# ADIS16209_Practice_Board.net
KiCad netlist of a schematic drawn in EAGLE
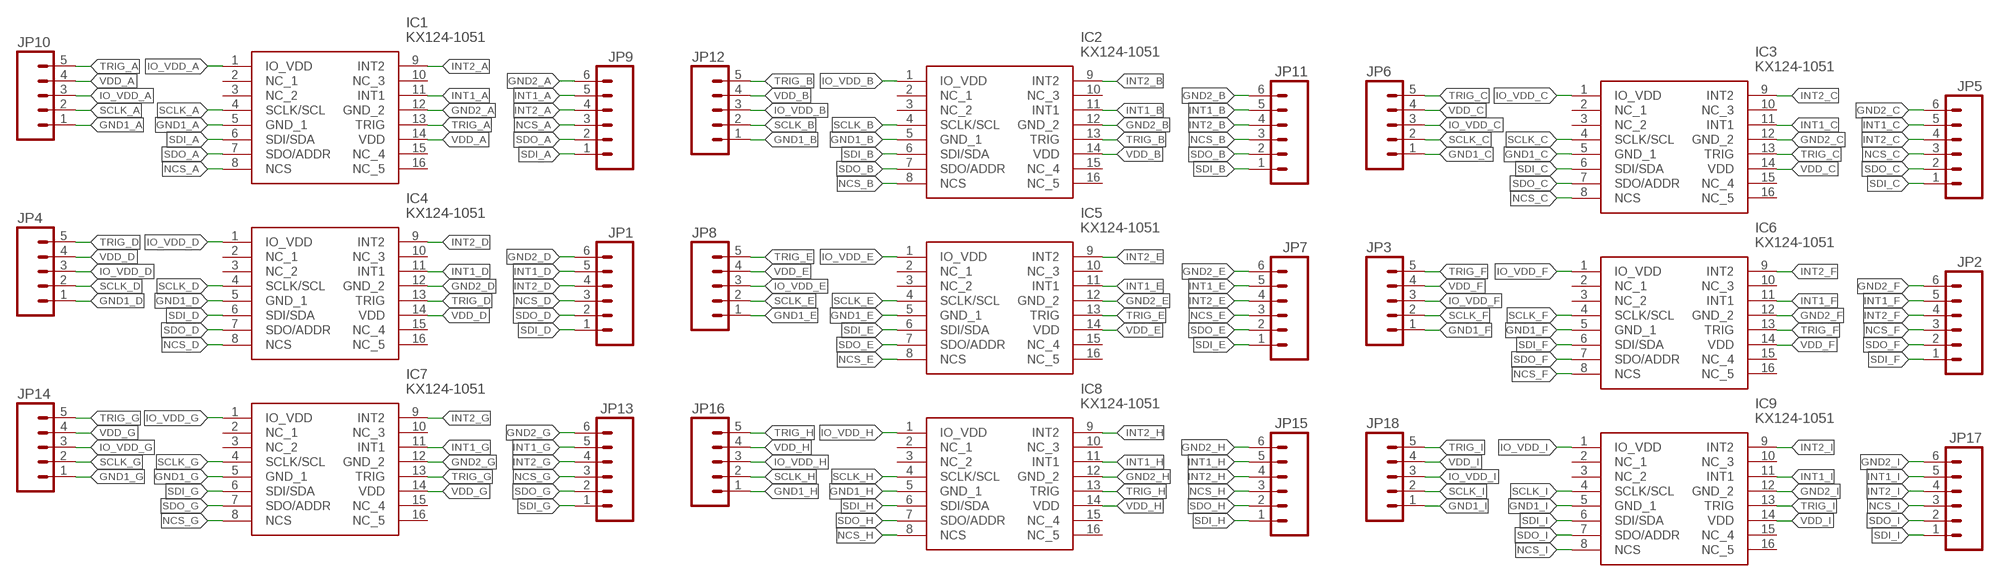
[diagram p0: schematic, sheet 1]

(export (version "E")
  (design (tool "Eeschema 10.0.6"))
  (components
    (comp (ref "IC1")
      (value "KX124-1051")
      (footprint "eagle-import:3X3LGA")
      (fields (field (name "MOUSER_PART_NUMBER") "912-KX124-1051-FR"))
      (libsource (lib "eagle-import") (part "KX124-1051"))
    )
    (comp (ref "IC2")
      (value "KX124-1051")
      (footprint "eagle-import:3X3LGA")
      (fields (field (name "MOUSER_PART_NUMBER") "912-KX124-1051-FR"))
      (libsource (lib "eagle-import") (part "KX124-1051"))
    )
    (comp (ref "IC3")
      (value "KX124-1051")
      (footprint "eagle-import:3X3LGA")
      (fields (field (name "MOUSER_PART_NUMBER") "912-KX124-1051-FR"))
      (libsource (lib "eagle-import") (part "KX124-1051"))
    )
    (comp (ref "IC4")
      (value "KX124-1051")
      (footprint "eagle-import:3X3LGA")
      (fields (field (name "MOUSER_PART_NUMBER") "912-KX124-1051-FR"))
      (libsource (lib "eagle-import") (part "KX124-1051"))
    )
    (comp (ref "IC5")
      (value "KX124-1051")
      (footprint "eagle-import:3X3LGA")
      (fields (field (name "MOUSER_PART_NUMBER") "912-KX124-1051-FR"))
      (libsource (lib "eagle-import") (part "KX124-1051"))
    )
    (comp (ref "IC6")
      (value "KX124-1051")
      (footprint "eagle-import:3X3LGA")
      (fields (field (name "MOUSER_PART_NUMBER") "912-KX124-1051-FR"))
      (libsource (lib "eagle-import") (part "KX124-1051"))
    )
    (comp (ref "IC7")
      (value "KX124-1051")
      (footprint "eagle-import:3X3LGA")
      (fields (field (name "MOUSER_PART_NUMBER") "912-KX124-1051-FR"))
      (libsource (lib "eagle-import") (part "KX124-1051"))
    )
    (comp (ref "IC8")
      (value "KX124-1051")
      (footprint "eagle-import:3X3LGA")
      (fields (field (name "MOUSER_PART_NUMBER") "912-KX124-1051-FR"))
      (libsource (lib "eagle-import") (part "KX124-1051"))
    )
    (comp (ref "IC9")
      (value "KX124-1051")
      (footprint "eagle-import:3X3LGA")
      (fields (field (name "MOUSER_PART_NUMBER") "912-KX124-1051-FR"))
      (libsource (lib "eagle-import") (part "KX124-1051"))
    )
    (comp (ref "JP1")
      (value "M06")
      (footprint "eagle-import:1X06")
      (libsource (lib "eagle-import") (part "M06"))
    )
    (comp (ref "JP2")
      (value "M06")
      (footprint "eagle-import:1X06")
      (libsource (lib "eagle-import") (part "M06"))
    )
    (comp (ref "JP3")
      (value "M05")
      (footprint "eagle-import:1X05")
      (libsource (lib "eagle-import") (part "M05"))
    )
    (comp (ref "JP4")
      (value "M05")
      (footprint "eagle-import:1X05")
      (libsource (lib "eagle-import") (part "M05"))
    )
    (comp (ref "JP5")
      (value "M06")
      (footprint "eagle-import:1X06")
      (libsource (lib "eagle-import") (part "M06"))
    )
    (comp (ref "JP6")
      (value "M05")
      (footprint "eagle-import:1X05")
      (libsource (lib "eagle-import") (part "M05"))
    )
    (comp (ref "JP7")
      (value "M06")
      (footprint "eagle-import:1X06")
      (libsource (lib "eagle-import") (part "M06"))
    )
    (comp (ref "JP8")
      (value "M05")
      (footprint "eagle-import:1X05")
      (libsource (lib "eagle-import") (part "M05"))
    )
    (comp (ref "JP9")
      (value "M06")
      (footprint "eagle-import:1X06")
      (libsource (lib "eagle-import") (part "M06"))
    )
    (comp (ref "JP10")
      (value "M05")
      (footprint "eagle-import:1X05")
      (libsource (lib "eagle-import") (part "M05"))
    )
    (comp (ref "JP11")
      (value "M06")
      (footprint "eagle-import:1X06")
      (libsource (lib "eagle-import") (part "M06"))
    )
    (comp (ref "JP12")
      (value "M05")
      (footprint "eagle-import:1X05")
      (libsource (lib "eagle-import") (part "M05"))
    )
    (comp (ref "JP13")
      (value "M06")
      (footprint "eagle-import:1X06")
      (libsource (lib "eagle-import") (part "M06"))
    )
    (comp (ref "JP14")
      (value "M05")
      (footprint "eagle-import:1X05")
      (libsource (lib "eagle-import") (part "M05"))
    )
    (comp (ref "JP15")
      (value "M06")
      (footprint "eagle-import:1X06")
      (libsource (lib "eagle-import") (part "M06"))
    )
    (comp (ref "JP16")
      (value "M05")
      (footprint "eagle-import:1X05")
      (libsource (lib "eagle-import") (part "M05"))
    )
    (comp (ref "JP17")
      (value "M06")
      (footprint "eagle-import:1X06")
      (libsource (lib "eagle-import") (part "M06"))
    )
    (comp (ref "JP18")
      (value "M05")
      (footprint "eagle-import:1X05")
      (libsource (lib "eagle-import") (part "M05"))
    )
  )
  (nets
    (net (code "1") (name "GND1_A") (class "Default")
      (node (ref "IC1") (pin "5") (pinfunction "GND_1_5") (pintype "bidirectional"))
      (node (ref "JP10") (pin "1") (pinfunction "1_1") (pintype "passive"))
    )
    (net (code "2") (name "GND1_B") (class "Default")
      (node (ref "IC2") (pin "5") (pinfunction "GND_1_5") (pintype "bidirectional"))
      (node (ref "JP12") (pin "1") (pinfunction "1_1") (pintype "passive"))
    )
    (net (code "3") (name "GND1_C") (class "Default")
      (node (ref "IC3") (pin "5") (pinfunction "GND_1_5") (pintype "bidirectional"))
      (node (ref "JP6") (pin "1") (pinfunction "1_1") (pintype "passive"))
    )
    (net (code "4") (name "GND1_D") (class "Default")
      (node (ref "IC4") (pin "5") (pinfunction "GND_1_5") (pintype "bidirectional"))
      (node (ref "JP4") (pin "1") (pinfunction "1_1") (pintype "passive"))
    )
    (net (code "5") (name "GND1_E") (class "Default")
      (node (ref "IC5") (pin "5") (pinfunction "GND_1_5") (pintype "bidirectional"))
      (node (ref "JP8") (pin "1") (pinfunction "1_1") (pintype "passive"))
    )
    (net (code "6") (name "GND1_F") (class "Default")
      (node (ref "IC6") (pin "5") (pinfunction "GND_1_5") (pintype "bidirectional"))
      (node (ref "JP3") (pin "1") (pinfunction "1_1") (pintype "passive"))
    )
    (net (code "7") (name "GND1_G") (class "Default")
      (node (ref "IC7") (pin "5") (pinfunction "GND_1_5") (pintype "bidirectional"))
      (node (ref "JP14") (pin "1") (pinfunction "1_1") (pintype "passive"))
    )
    (net (code "8") (name "GND1_H") (class "Default")
      (node (ref "IC8") (pin "5") (pinfunction "GND_1_5") (pintype "bidirectional"))
      (node (ref "JP16") (pin "1") (pinfunction "1_1") (pintype "passive"))
    )
    (net (code "9") (name "GND1_I") (class "Default")
      (node (ref "IC9") (pin "5") (pinfunction "GND_1_5") (pintype "bidirectional"))
      (node (ref "JP18") (pin "1") (pinfunction "1_1") (pintype "passive"))
    )
    (net (code "10") (name "GND2_A") (class "Default")
      (node (ref "IC1") (pin "12") (pinfunction "GND_2_12") (pintype "bidirectional"))
      (node (ref "JP9") (pin "6") (pinfunction "6_6") (pintype "passive"))
    )
    (net (code "11") (name "GND2_B") (class "Default")
      (node (ref "IC2") (pin "12") (pinfunction "GND_2_12") (pintype "bidirectional"))
      (node (ref "JP11") (pin "6") (pinfunction "6_6") (pintype "passive"))
    )
    (net (code "12") (name "GND2_C") (class "Default")
      (node (ref "IC3") (pin "12") (pinfunction "GND_2_12") (pintype "bidirectional"))
      (node (ref "JP5") (pin "6") (pinfunction "6_6") (pintype "passive"))
    )
    (net (code "13") (name "GND2_D") (class "Default")
      (node (ref "IC4") (pin "12") (pinfunction "GND_2_12") (pintype "bidirectional"))
      (node (ref "JP1") (pin "6") (pinfunction "6_6") (pintype "passive"))
    )
    (net (code "14") (name "GND2_E") (class "Default")
      (node (ref "IC5") (pin "12") (pinfunction "GND_2_12") (pintype "bidirectional"))
      (node (ref "JP7") (pin "6") (pinfunction "6_6") (pintype "passive"))
    )
    (net (code "15") (name "GND2_F") (class "Default")
      (node (ref "IC6") (pin "12") (pinfunction "GND_2_12") (pintype "bidirectional"))
      (node (ref "JP2") (pin "6") (pinfunction "6_6") (pintype "passive"))
    )
    (net (code "16") (name "GND2_G") (class "Default")
      (node (ref "IC7") (pin "12") (pinfunction "GND_2_12") (pintype "bidirectional"))
      (node (ref "JP13") (pin "6") (pinfunction "6_6") (pintype "passive"))
    )
    (net (code "17") (name "GND2_H") (class "Default")
      (node (ref "IC8") (pin "12") (pinfunction "GND_2_12") (pintype "bidirectional"))
      (node (ref "JP15") (pin "6") (pinfunction "6_6") (pintype "passive"))
    )
    (net (code "18") (name "GND2_I") (class "Default")
      (node (ref "IC9") (pin "12") (pinfunction "GND_2_12") (pintype "bidirectional"))
      (node (ref "JP17") (pin "6") (pinfunction "6_6") (pintype "passive"))
    )
    (net (code "19") (name "INT1_A") (class "Default")
      (node (ref "IC1") (pin "11") (pinfunction "INT1_11") (pintype "bidirectional"))
      (node (ref "JP9") (pin "5") (pinfunction "5_5") (pintype "passive"))
    )
    (net (code "20") (name "INT1_B") (class "Default")
      (node (ref "IC2") (pin "11") (pinfunction "INT1_11") (pintype "bidirectional"))
      (node (ref "JP11") (pin "5") (pinfunction "5_5") (pintype "passive"))
    )
    (net (code "21") (name "INT1_C") (class "Default")
      (node (ref "IC3") (pin "11") (pinfunction "INT1_11") (pintype "bidirectional"))
      (node (ref "JP5") (pin "5") (pinfunction "5_5") (pintype "passive"))
    )
    (net (code "22") (name "INT1_D") (class "Default")
      (node (ref "IC4") (pin "11") (pinfunction "INT1_11") (pintype "bidirectional"))
      (node (ref "JP1") (pin "5") (pinfunction "5_5") (pintype "passive"))
    )
    (net (code "23") (name "INT1_E") (class "Default")
      (node (ref "IC5") (pin "11") (pinfunction "INT1_11") (pintype "bidirectional"))
      (node (ref "JP7") (pin "5") (pinfunction "5_5") (pintype "passive"))
    )
    (net (code "24") (name "INT1_F") (class "Default")
      (node (ref "IC6") (pin "11") (pinfunction "INT1_11") (pintype "bidirectional"))
      (node (ref "JP2") (pin "5") (pinfunction "5_5") (pintype "passive"))
    )
    (net (code "25") (name "INT1_G") (class "Default")
      (node (ref "IC7") (pin "11") (pinfunction "INT1_11") (pintype "bidirectional"))
      (node (ref "JP13") (pin "5") (pinfunction "5_5") (pintype "passive"))
    )
    (net (code "26") (name "INT1_H") (class "Default")
      (node (ref "IC8") (pin "11") (pinfunction "INT1_11") (pintype "bidirectional"))
      (node (ref "JP15") (pin "5") (pinfunction "5_5") (pintype "passive"))
    )
    (net (code "27") (name "INT1_I") (class "Default")
      (node (ref "IC9") (pin "11") (pinfunction "INT1_11") (pintype "bidirectional"))
      (node (ref "JP17") (pin "5") (pinfunction "5_5") (pintype "passive"))
    )
    (net (code "28") (name "INT2_A") (class "Default")
      (node (ref "IC1") (pin "9") (pinfunction "INT2_9") (pintype "bidirectional"))
      (node (ref "JP9") (pin "4") (pinfunction "4_4") (pintype "passive"))
    )
    (net (code "29") (name "INT2_B") (class "Default")
      (node (ref "IC2") (pin "9") (pinfunction "INT2_9") (pintype "bidirectional"))
      (node (ref "JP11") (pin "4") (pinfunction "4_4") (pintype "passive"))
    )
    (net (code "30") (name "INT2_C") (class "Default")
      (node (ref "IC3") (pin "9") (pinfunction "INT2_9") (pintype "bidirectional"))
      (node (ref "JP5") (pin "4") (pinfunction "4_4") (pintype "passive"))
    )
    (net (code "31") (name "INT2_D") (class "Default")
      (node (ref "IC4") (pin "9") (pinfunction "INT2_9") (pintype "bidirectional"))
      (node (ref "JP1") (pin "4") (pinfunction "4_4") (pintype "passive"))
    )
    (net (code "32") (name "INT2_E") (class "Default")
      (node (ref "IC5") (pin "9") (pinfunction "INT2_9") (pintype "bidirectional"))
      (node (ref "JP7") (pin "4") (pinfunction "4_4") (pintype "passive"))
    )
    (net (code "33") (name "INT2_F") (class "Default")
      (node (ref "IC6") (pin "9") (pinfunction "INT2_9") (pintype "bidirectional"))
      (node (ref "JP2") (pin "4") (pinfunction "4_4") (pintype "passive"))
    )
    (net (code "34") (name "INT2_G") (class "Default")
      (node (ref "IC7") (pin "9") (pinfunction "INT2_9") (pintype "bidirectional"))
      (node (ref "JP13") (pin "4") (pinfunction "4_4") (pintype "passive"))
    )
    (net (code "35") (name "INT2_H") (class "Default")
      (node (ref "IC8") (pin "9") (pinfunction "INT2_9") (pintype "bidirectional"))
      (node (ref "JP15") (pin "4") (pinfunction "4_4") (pintype "passive"))
    )
    (net (code "36") (name "INT2_I") (class "Default")
      (node (ref "IC9") (pin "9") (pinfunction "INT2_9") (pintype "bidirectional"))
      (node (ref "JP17") (pin "4") (pinfunction "4_4") (pintype "passive"))
    )
    (net (code "37") (name "IO_VDD_A") (class "Default")
      (node (ref "IC1") (pin "1") (pinfunction "IO_VDD_1") (pintype "bidirectional"))
      (node (ref "JP10") (pin "3") (pinfunction "3_3") (pintype "passive"))
    )
    (net (code "38") (name "IO_VDD_B") (class "Default")
      (node (ref "IC2") (pin "1") (pinfunction "IO_VDD_1") (pintype "bidirectional"))
      (node (ref "JP12") (pin "3") (pinfunction "3_3") (pintype "passive"))
    )
    (net (code "39") (name "IO_VDD_C") (class "Default")
      (node (ref "IC3") (pin "1") (pinfunction "IO_VDD_1") (pintype "bidirectional"))
      (node (ref "JP6") (pin "3") (pinfunction "3_3") (pintype "passive"))
    )
    (net (code "40") (name "IO_VDD_D") (class "Default")
      (node (ref "IC4") (pin "1") (pinfunction "IO_VDD_1") (pintype "bidirectional"))
      (node (ref "JP4") (pin "3") (pinfunction "3_3") (pintype "passive"))
    )
    (net (code "41") (name "IO_VDD_E") (class "Default")
      (node (ref "IC5") (pin "1") (pinfunction "IO_VDD_1") (pintype "bidirectional"))
      (node (ref "JP8") (pin "3") (pinfunction "3_3") (pintype "passive"))
    )
    (net (code "42") (name "IO_VDD_F") (class "Default")
      (node (ref "IC6") (pin "1") (pinfunction "IO_VDD_1") (pintype "bidirectional"))
      (node (ref "JP3") (pin "3") (pinfunction "3_3") (pintype "passive"))
    )
    (net (code "43") (name "IO_VDD_G") (class "Default")
      (node (ref "IC7") (pin "1") (pinfunction "IO_VDD_1") (pintype "bidirectional"))
      (node (ref "JP14") (pin "3") (pinfunction "3_3") (pintype "passive"))
    )
    (net (code "44") (name "IO_VDD_H") (class "Default")
      (node (ref "IC8") (pin "1") (pinfunction "IO_VDD_1") (pintype "bidirectional"))
      (node (ref "JP16") (pin "3") (pinfunction "3_3") (pintype "passive"))
    )
    (net (code "45") (name "IO_VDD_I") (class "Default")
      (node (ref "IC9") (pin "1") (pinfunction "IO_VDD_1") (pintype "bidirectional"))
      (node (ref "JP18") (pin "3") (pinfunction "3_3") (pintype "passive"))
    )
    (net (code "46") (name "NCS_A") (class "Default")
      (node (ref "IC1") (pin "8") (pinfunction "NCS_8") (pintype "bidirectional"))
      (node (ref "JP9") (pin "3") (pinfunction "3_3") (pintype "passive"))
    )
    (net (code "47") (name "NCS_B") (class "Default")
      (node (ref "IC2") (pin "8") (pinfunction "NCS_8") (pintype "bidirectional"))
      (node (ref "JP11") (pin "3") (pinfunction "3_3") (pintype "passive"))
    )
    (net (code "48") (name "NCS_C") (class "Default")
      (node (ref "IC3") (pin "8") (pinfunction "NCS_8") (pintype "bidirectional"))
      (node (ref "JP5") (pin "3") (pinfunction "3_3") (pintype "passive"))
    )
    (net (code "49") (name "NCS_D") (class "Default")
      (node (ref "IC4") (pin "8") (pinfunction "NCS_8") (pintype "bidirectional"))
      (node (ref "JP1") (pin "3") (pinfunction "3_3") (pintype "passive"))
    )
    (net (code "50") (name "NCS_E") (class "Default")
      (node (ref "IC5") (pin "8") (pinfunction "NCS_8") (pintype "bidirectional"))
      (node (ref "JP7") (pin "3") (pinfunction "3_3") (pintype "passive"))
    )
    (net (code "51") (name "NCS_F") (class "Default")
      (node (ref "IC6") (pin "8") (pinfunction "NCS_8") (pintype "bidirectional"))
      (node (ref "JP2") (pin "3") (pinfunction "3_3") (pintype "passive"))
    )
    (net (code "52") (name "NCS_G") (class "Default")
      (node (ref "IC7") (pin "8") (pinfunction "NCS_8") (pintype "bidirectional"))
      (node (ref "JP13") (pin "3") (pinfunction "3_3") (pintype "passive"))
    )
    (net (code "53") (name "NCS_H") (class "Default")
      (node (ref "IC8") (pin "8") (pinfunction "NCS_8") (pintype "bidirectional"))
      (node (ref "JP15") (pin "3") (pinfunction "3_3") (pintype "passive"))
    )
    (net (code "54") (name "NCS_I") (class "Default")
      (node (ref "IC9") (pin "8") (pinfunction "NCS_8") (pintype "bidirectional"))
      (node (ref "JP17") (pin "3") (pinfunction "3_3") (pintype "passive"))
    )
    (net (code "55") (name "SCLK_A") (class "Default")
      (node (ref "IC1") (pin "4") (pinfunction "SCLK/SCL_4") (pintype "bidirectional"))
      (node (ref "JP10") (pin "2") (pinfunction "2_2") (pintype "passive"))
    )
    (net (code "56") (name "SCLK_B") (class "Default")
      (node (ref "IC2") (pin "4") (pinfunction "SCLK/SCL_4") (pintype "bidirectional"))
      (node (ref "JP12") (pin "2") (pinfunction "2_2") (pintype "passive"))
    )
    (net (code "57") (name "SCLK_C") (class "Default")
      (node (ref "IC3") (pin "4") (pinfunction "SCLK/SCL_4") (pintype "bidirectional"))
      (node (ref "JP6") (pin "2") (pinfunction "2_2") (pintype "passive"))
    )
    (net (code "58") (name "SCLK_D") (class "Default")
      (node (ref "IC4") (pin "4") (pinfunction "SCLK/SCL_4") (pintype "bidirectional"))
      (node (ref "JP4") (pin "2") (pinfunction "2_2") (pintype "passive"))
    )
    (net (code "59") (name "SCLK_E") (class "Default")
      (node (ref "IC5") (pin "4") (pinfunction "SCLK/SCL_4") (pintype "bidirectional"))
      (node (ref "JP8") (pin "2") (pinfunction "2_2") (pintype "passive"))
    )
    (net (code "60") (name "SCLK_F") (class "Default")
      (node (ref "IC6") (pin "4") (pinfunction "SCLK/SCL_4") (pintype "bidirectional"))
      (node (ref "JP3") (pin "2") (pinfunction "2_2") (pintype "passive"))
    )
    (net (code "61") (name "SCLK_G") (class "Default")
      (node (ref "IC7") (pin "4") (pinfunction "SCLK/SCL_4") (pintype "bidirectional"))
      (node (ref "JP14") (pin "2") (pinfunction "2_2") (pintype "passive"))
    )
    (net (code "62") (name "SCLK_H") (class "Default")
      (node (ref "IC8") (pin "4") (pinfunction "SCLK/SCL_4") (pintype "bidirectional"))
      (node (ref "JP16") (pin "2") (pinfunction "2_2") (pintype "passive"))
    )
    (net (code "63") (name "SCLK_I") (class "Default")
      (node (ref "IC9") (pin "4") (pinfunction "SCLK/SCL_4") (pintype "bidirectional"))
      (node (ref "JP18") (pin "2") (pinfunction "2_2") (pintype "passive"))
    )
    (net (code "64") (name "SDI_A") (class "Default")
      (node (ref "IC1") (pin "6") (pinfunction "SDI/SDA_6") (pintype "bidirectional"))
      (node (ref "JP9") (pin "1") (pinfunction "1_1") (pintype "passive"))
    )
    (net (code "65") (name "SDI_B") (class "Default")
      (node (ref "IC2") (pin "6") (pinfunction "SDI/SDA_6") (pintype "bidirectional"))
      (node (ref "JP11") (pin "1") (pinfunction "1_1") (pintype "passive"))
    )
    (net (code "66") (name "SDI_C") (class "Default")
      (node (ref "IC3") (pin "6") (pinfunction "SDI/SDA_6") (pintype "bidirectional"))
      (node (ref "JP5") (pin "1") (pinfunction "1_1") (pintype "passive"))
    )
    (net (code "67") (name "SDI_D") (class "Default")
      (node (ref "IC4") (pin "6") (pinfunction "SDI/SDA_6") (pintype "bidirectional"))
      (node (ref "JP1") (pin "1") (pinfunction "1_1") (pintype "passive"))
    )
    (net (code "68") (name "SDI_E") (class "Default")
      (node (ref "IC5") (pin "6") (pinfunction "SDI/SDA_6") (pintype "bidirectional"))
      (node (ref "JP7") (pin "1") (pinfunction "1_1") (pintype "passive"))
    )
    (net (code "69") (name "SDI_F") (class "Default")
      (node (ref "IC6") (pin "6") (pinfunction "SDI/SDA_6") (pintype "bidirectional"))
      (node (ref "JP2") (pin "1") (pinfunction "1_1") (pintype "passive"))
    )
    (net (code "70") (name "SDI_G") (class "Default")
      (node (ref "IC7") (pin "6") (pinfunction "SDI/SDA_6") (pintype "bidirectional"))
      (node (ref "JP13") (pin "1") (pinfunction "1_1") (pintype "passive"))
    )
    (net (code "71") (name "SDI_H") (class "Default")
      (node (ref "IC8") (pin "6") (pinfunction "SDI/SDA_6") (pintype "bidirectional"))
      (node (ref "JP15") (pin "1") (pinfunction "1_1") (pintype "passive"))
    )
    (net (code "72") (name "SDI_I") (class "Default")
      (node (ref "IC9") (pin "6") (pinfunction "SDI/SDA_6") (pintype "bidirectional"))
      (node (ref "JP17") (pin "1") (pinfunction "1_1") (pintype "passive"))
    )
    (net (code "73") (name "SDO_A") (class "Default")
      (node (ref "IC1") (pin "7") (pinfunction "SDO/ADDR_7") (pintype "bidirectional"))
      (node (ref "JP9") (pin "2") (pinfunction "2_2") (pintype "passive"))
    )
    (net (code "74") (name "SDO_B") (class "Default")
      (node (ref "IC2") (pin "7") (pinfunction "SDO/ADDR_7") (pintype "bidirectional"))
      (node (ref "JP11") (pin "2") (pinfunction "2_2") (pintype "passive"))
    )
    (net (code "75") (name "SDO_C") (class "Default")
      (node (ref "IC3") (pin "7") (pinfunction "SDO/ADDR_7") (pintype "bidirectional"))
      (node (ref "JP5") (pin "2") (pinfunction "2_2") (pintype "passive"))
    )
    (net (code "76") (name "SDO_D") (class "Default")
      (node (ref "IC4") (pin "7") (pinfunction "SDO/ADDR_7") (pintype "bidirectional"))
      (node (ref "JP1") (pin "2") (pinfunction "2_2") (pintype "passive"))
    )
    (net (code "77") (name "SDO_E") (class "Default")
      (node (ref "IC5") (pin "7") (pinfunction "SDO/ADDR_7") (pintype "bidirectional"))
      (node (ref "JP7") (pin "2") (pinfunction "2_2") (pintype "passive"))
    )
    (net (code "78") (name "SDO_F") (class "Default")
      (node (ref "IC6") (pin "7") (pinfunction "SDO/ADDR_7") (pintype "bidirectional"))
      (node (ref "JP2") (pin "2") (pinfunction "2_2") (pintype "passive"))
    )
    (net (code "79") (name "SDO_G") (class "Default")
      (node (ref "IC7") (pin "7") (pinfunction "SDO/ADDR_7") (pintype "bidirectional"))
      (node (ref "JP13") (pin "2") (pinfunction "2_2") (pintype "passive"))
    )
    (net (code "80") (name "SDO_H") (class "Default")
      (node (ref "IC8") (pin "7") (pinfunction "SDO/ADDR_7") (pintype "bidirectional"))
      (node (ref "JP15") (pin "2") (pinfunction "2_2") (pintype "passive"))
    )
    (net (code "81") (name "SDO_I") (class "Default")
      (node (ref "IC9") (pin "7") (pinfunction "SDO/ADDR_7") (pintype "bidirectional"))
      (node (ref "JP17") (pin "2") (pinfunction "2_2") (pintype "passive"))
    )
    (net (code "82") (name "TRIG_A") (class "Default")
      (node (ref "IC1") (pin "13") (pinfunction "TRIG_13") (pintype "bidirectional"))
      (node (ref "JP10") (pin "5") (pinfunction "5_5") (pintype "passive"))
    )
    (net (code "83") (name "TRIG_B") (class "Default")
      (node (ref "IC2") (pin "13") (pinfunction "TRIG_13") (pintype "bidirectional"))
      (node (ref "JP12") (pin "5") (pinfunction "5_5") (pintype "passive"))
    )
    (net (code "84") (name "TRIG_C") (class "Default")
      (node (ref "IC3") (pin "13") (pinfunction "TRIG_13") (pintype "bidirectional"))
      (node (ref "JP6") (pin "5") (pinfunction "5_5") (pintype "passive"))
    )
    (net (code "85") (name "TRIG_D") (class "Default")
      (node (ref "IC4") (pin "13") (pinfunction "TRIG_13") (pintype "bidirectional"))
      (node (ref "JP4") (pin "5") (pinfunction "5_5") (pintype "passive"))
    )
    (net (code "86") (name "TRIG_E") (class "Default")
      (node (ref "IC5") (pin "13") (pinfunction "TRIG_13") (pintype "bidirectional"))
      (node (ref "JP8") (pin "5") (pinfunction "5_5") (pintype "passive"))
    )
    (net (code "87") (name "TRIG_F") (class "Default")
      (node (ref "IC6") (pin "13") (pinfunction "TRIG_13") (pintype "bidirectional"))
      (node (ref "JP3") (pin "5") (pinfunction "5_5") (pintype "passive"))
    )
    (net (code "88") (name "TRIG_G") (class "Default")
      (node (ref "IC7") (pin "13") (pinfunction "TRIG_13") (pintype "bidirectional"))
      (node (ref "JP14") (pin "5") (pinfunction "5_5") (pintype "passive"))
    )
    (net (code "89") (name "TRIG_H") (class "Default")
      (node (ref "IC8") (pin "13") (pinfunction "TRIG_13") (pintype "bidirectional"))
      (node (ref "JP16") (pin "5") (pinfunction "5_5") (pintype "passive"))
    )
    (net (code "90") (name "TRIG_I") (class "Default")
      (node (ref "IC9") (pin "13") (pinfunction "TRIG_13") (pintype "bidirectional"))
      (node (ref "JP18") (pin "5") (pinfunction "5_5") (pintype "passive"))
    )
    (net (code "91") (name "VDD_A") (class "Default")
      (node (ref "IC1") (pin "14") (pinfunction "VDD_14") (pintype "bidirectional"))
      (node (ref "JP10") (pin "4") (pinfunction "4_4") (pintype "passive"))
    )
    (net (code "92") (name "VDD_B") (class "Default")
      (node (ref "IC2") (pin "14") (pinfunction "VDD_14") (pintype "bidirectional"))
      (node (ref "JP12") (pin "4") (pinfunction "4_4") (pintype "passive"))
    )
    (net (code "93") (name "VDD_C") (class "Default")
      (node (ref "IC3") (pin "14") (pinfunction "VDD_14") (pintype "bidirectional"))
      (node (ref "JP6") (pin "4") (pinfunction "4_4") (pintype "passive"))
    )
    (net (code "94") (name "VDD_D") (class "Default")
      (node (ref "IC4") (pin "14") (pinfunction "VDD_14") (pintype "bidirectional"))
      (node (ref "JP4") (pin "4") (pinfunction "4_4") (pintype "passive"))
    )
    (net (code "95") (name "VDD_E") (class "Default")
      (node (ref "IC5") (pin "14") (pinfunction "VDD_14") (pintype "bidirectional"))
      (node (ref "JP8") (pin "4") (pinfunction "4_4") (pintype "passive"))
    )
    (net (code "96") (name "VDD_F") (class "Default")
      (node (ref "IC6") (pin "14") (pinfunction "VDD_14") (pintype "bidirectional"))
      (node (ref "JP3") (pin "4") (pinfunction "4_4") (pintype "passive"))
    )
    (net (code "97") (name "VDD_G") (class "Default")
      (node (ref "IC7") (pin "14") (pinfunction "VDD_14") (pintype "bidirectional"))
      (node (ref "JP14") (pin "4") (pinfunction "4_4") (pintype "passive"))
    )
    (net (code "98") (name "VDD_H") (class "Default")
      (node (ref "IC8") (pin "14") (pinfunction "VDD_14") (pintype "bidirectional"))
      (node (ref "JP16") (pin "4") (pinfunction "4_4") (pintype "passive"))
    )
    (net (code "99") (name "VDD_I") (class "Default")
      (node (ref "IC9") (pin "14") (pinfunction "VDD_14") (pintype "bidirectional"))
      (node (ref "JP18") (pin "4") (pinfunction "4_4") (pintype "passive"))
    )
    (net (code "100") (name "unconnected-(IC1-NC_1-Pad2)") (class "Default")
      (node (ref "IC1") (pin "2") (pinfunction "NC_1_2") (pintype "bidirectional"))
    )
    (net (code "101") (name "unconnected-(IC1-NC_2-Pad3)") (class "Default")
      (node (ref "IC1") (pin "3") (pinfunction "NC_2_3") (pintype "bidirectional"))
    )
    (net (code "102") (name "unconnected-(IC1-NC_3-Pad10)") (class "Default")
      (node (ref "IC1") (pin "10") (pinfunction "NC_3_10") (pintype "bidirectional"))
    )
    (net (code "103") (name "unconnected-(IC1-NC_4-Pad15)") (class "Default")
      (node (ref "IC1") (pin "15") (pinfunction "NC_4_15") (pintype "bidirectional"))
    )
    (net (code "104") (name "unconnected-(IC1-NC_5-Pad16)") (class "Default")
      (node (ref "IC1") (pin "16") (pinfunction "NC_5_16") (pintype "bidirectional"))
    )
    (net (code "105") (name "unconnected-(IC2-NC_1-Pad2)") (class "Default")
      (node (ref "IC2") (pin "2") (pinfunction "NC_1_2") (pintype "bidirectional"))
    )
    (net (code "106") (name "unconnected-(IC2-NC_2-Pad3)") (class "Default")
      (node (ref "IC2") (pin "3") (pinfunction "NC_2_3") (pintype "bidirectional"))
    )
    (net (code "107") (name "unconnected-(IC2-NC_3-Pad10)") (class "Default")
      (node (ref "IC2") (pin "10") (pinfunction "NC_3_10") (pintype "bidirectional"))
    )
    (net (code "108") (name "unconnected-(IC2-NC_4-Pad15)") (class "Default")
      (node (ref "IC2") (pin "15") (pinfunction "NC_4_15") (pintype "bidirectional"))
    )
    (net (code "109") (name "unconnected-(IC2-NC_5-Pad16)") (class "Default")
      (node (ref "IC2") (pin "16") (pinfunction "NC_5_16") (pintype "bidirectional"))
    )
    (net (code "110") (name "unconnected-(IC3-NC_1-Pad2)") (class "Default")
      (node (ref "IC3") (pin "2") (pinfunction "NC_1_2") (pintype "bidirectional"))
    )
    (net (code "111") (name "unconnected-(IC3-NC_2-Pad3)") (class "Default")
      (node (ref "IC3") (pin "3") (pinfunction "NC_2_3") (pintype "bidirectional"))
    )
    (net (code "112") (name "unconnected-(IC3-NC_3-Pad10)") (class "Default")
      (node (ref "IC3") (pin "10") (pinfunction "NC_3_10") (pintype "bidirectional"))
    )
    (net (code "113") (name "unconnected-(IC3-NC_4-Pad15)") (class "Default")
      (node (ref "IC3") (pin "15") (pinfunction "NC_4_15") (pintype "bidirectional"))
    )
    (net (code "114") (name "unconnected-(IC3-NC_5-Pad16)") (class "Default")
      (node (ref "IC3") (pin "16") (pinfunction "NC_5_16") (pintype "bidirectional"))
    )
    (net (code "115") (name "unconnected-(IC4-NC_1-Pad2)") (class "Default")
      (node (ref "IC4") (pin "2") (pinfunction "NC_1_2") (pintype "bidirectional"))
    )
    (net (code "116") (name "unconnected-(IC4-NC_2-Pad3)") (class "Default")
      (node (ref "IC4") (pin "3") (pinfunction "NC_2_3") (pintype "bidirectional"))
    )
    (net (code "117") (name "unconnected-(IC4-NC_3-Pad10)") (class "Default")
      (node (ref "IC4") (pin "10") (pinfunction "NC_3_10") (pintype "bidirectional"))
    )
    (net (code "118") (name "unconnected-(IC4-NC_4-Pad15)") (class "Default")
      (node (ref "IC4") (pin "15") (pinfunction "NC_4_15") (pintype "bidirectional"))
    )
    (net (code "119") (name "unconnected-(IC4-NC_5-Pad16)") (class "Default")
      (node (ref "IC4") (pin "16") (pinfunction "NC_5_16") (pintype "bidirectional"))
    )
    (net (code "120") (name "unconnected-(IC5-NC_1-Pad2)") (class "Default")
      (node (ref "IC5") (pin "2") (pinfunction "NC_1_2") (pintype "bidirectional"))
    )
    (net (code "121") (name "unconnected-(IC5-NC_2-Pad3)") (class "Default")
      (node (ref "IC5") (pin "3") (pinfunction "NC_2_3") (pintype "bidirectional"))
    )
    (net (code "122") (name "unconnected-(IC5-NC_3-Pad10)") (class "Default")
      (node (ref "IC5") (pin "10") (pinfunction "NC_3_10") (pintype "bidirectional"))
    )
    (net (code "123") (name "unconnected-(IC5-NC_4-Pad15)") (class "Default")
      (node (ref "IC5") (pin "15") (pinfunction "NC_4_15") (pintype "bidirectional"))
    )
    (net (code "124") (name "unconnected-(IC5-NC_5-Pad16)") (class "Default")
      (node (ref "IC5") (pin "16") (pinfunction "NC_5_16") (pintype "bidirectional"))
    )
    (net (code "125") (name "unconnected-(IC6-NC_1-Pad2)") (class "Default")
      (node (ref "IC6") (pin "2") (pinfunction "NC_1_2") (pintype "bidirectional"))
    )
    (net (code "126") (name "unconnected-(IC6-NC_2-Pad3)") (class "Default")
      (node (ref "IC6") (pin "3") (pinfunction "NC_2_3") (pintype "bidirectional"))
    )
    (net (code "127") (name "unconnected-(IC6-NC_3-Pad10)") (class "Default")
      (node (ref "IC6") (pin "10") (pinfunction "NC_3_10") (pintype "bidirectional"))
    )
    (net (code "128") (name "unconnected-(IC6-NC_4-Pad15)") (class "Default")
      (node (ref "IC6") (pin "15") (pinfunction "NC_4_15") (pintype "bidirectional"))
    )
    (net (code "129") (name "unconnected-(IC6-NC_5-Pad16)") (class "Default")
      (node (ref "IC6") (pin "16") (pinfunction "NC_5_16") (pintype "bidirectional"))
    )
    (net (code "130") (name "unconnected-(IC7-NC_1-Pad2)") (class "Default")
      (node (ref "IC7") (pin "2") (pinfunction "NC_1_2") (pintype "bidirectional"))
    )
    (net (code "131") (name "unconnected-(IC7-NC_2-Pad3)") (class "Default")
      (node (ref "IC7") (pin "3") (pinfunction "NC_2_3") (pintype "bidirectional"))
    )
    (net (code "132") (name "unconnected-(IC7-NC_3-Pad10)") (class "Default")
      (node (ref "IC7") (pin "10") (pinfunction "NC_3_10") (pintype "bidirectional"))
    )
    (net (code "133") (name "unconnected-(IC7-NC_4-Pad15)") (class "Default")
      (node (ref "IC7") (pin "15") (pinfunction "NC_4_15") (pintype "bidirectional"))
    )
    (net (code "134") (name "unconnected-(IC7-NC_5-Pad16)") (class "Default")
      (node (ref "IC7") (pin "16") (pinfunction "NC_5_16") (pintype "bidirectional"))
    )
    (net (code "135") (name "unconnected-(IC8-NC_1-Pad2)") (class "Default")
      (node (ref "IC8") (pin "2") (pinfunction "NC_1_2") (pintype "bidirectional"))
    )
    (net (code "136") (name "unconnected-(IC8-NC_2-Pad3)") (class "Default")
      (node (ref "IC8") (pin "3") (pinfunction "NC_2_3") (pintype "bidirectional"))
    )
    (net (code "137") (name "unconnected-(IC8-NC_3-Pad10)") (class "Default")
      (node (ref "IC8") (pin "10") (pinfunction "NC_3_10") (pintype "bidirectional"))
    )
    (net (code "138") (name "unconnected-(IC8-NC_4-Pad15)") (class "Default")
      (node (ref "IC8") (pin "15") (pinfunction "NC_4_15") (pintype "bidirectional"))
    )
    (net (code "139") (name "unconnected-(IC8-NC_5-Pad16)") (class "Default")
      (node (ref "IC8") (pin "16") (pinfunction "NC_5_16") (pintype "bidirectional"))
    )
    (net (code "140") (name "unconnected-(IC9-NC_1-Pad2)") (class "Default")
      (node (ref "IC9") (pin "2") (pinfunction "NC_1_2") (pintype "bidirectional"))
    )
    (net (code "141") (name "unconnected-(IC9-NC_2-Pad3)") (class "Default")
      (node (ref "IC9") (pin "3") (pinfunction "NC_2_3") (pintype "bidirectional"))
    )
    (net (code "142") (name "unconnected-(IC9-NC_3-Pad10)") (class "Default")
      (node (ref "IC9") (pin "10") (pinfunction "NC_3_10") (pintype "bidirectional"))
    )
    (net (code "143") (name "unconnected-(IC9-NC_4-Pad15)") (class "Default")
      (node (ref "IC9") (pin "15") (pinfunction "NC_4_15") (pintype "bidirectional"))
    )
    (net (code "144") (name "unconnected-(IC9-NC_5-Pad16)") (class "Default")
      (node (ref "IC9") (pin "16") (pinfunction "NC_5_16") (pintype "bidirectional"))
    )
  )
)
